# trezor_nuri.net
KiCad netlist of a schematic drawn in EAGLE
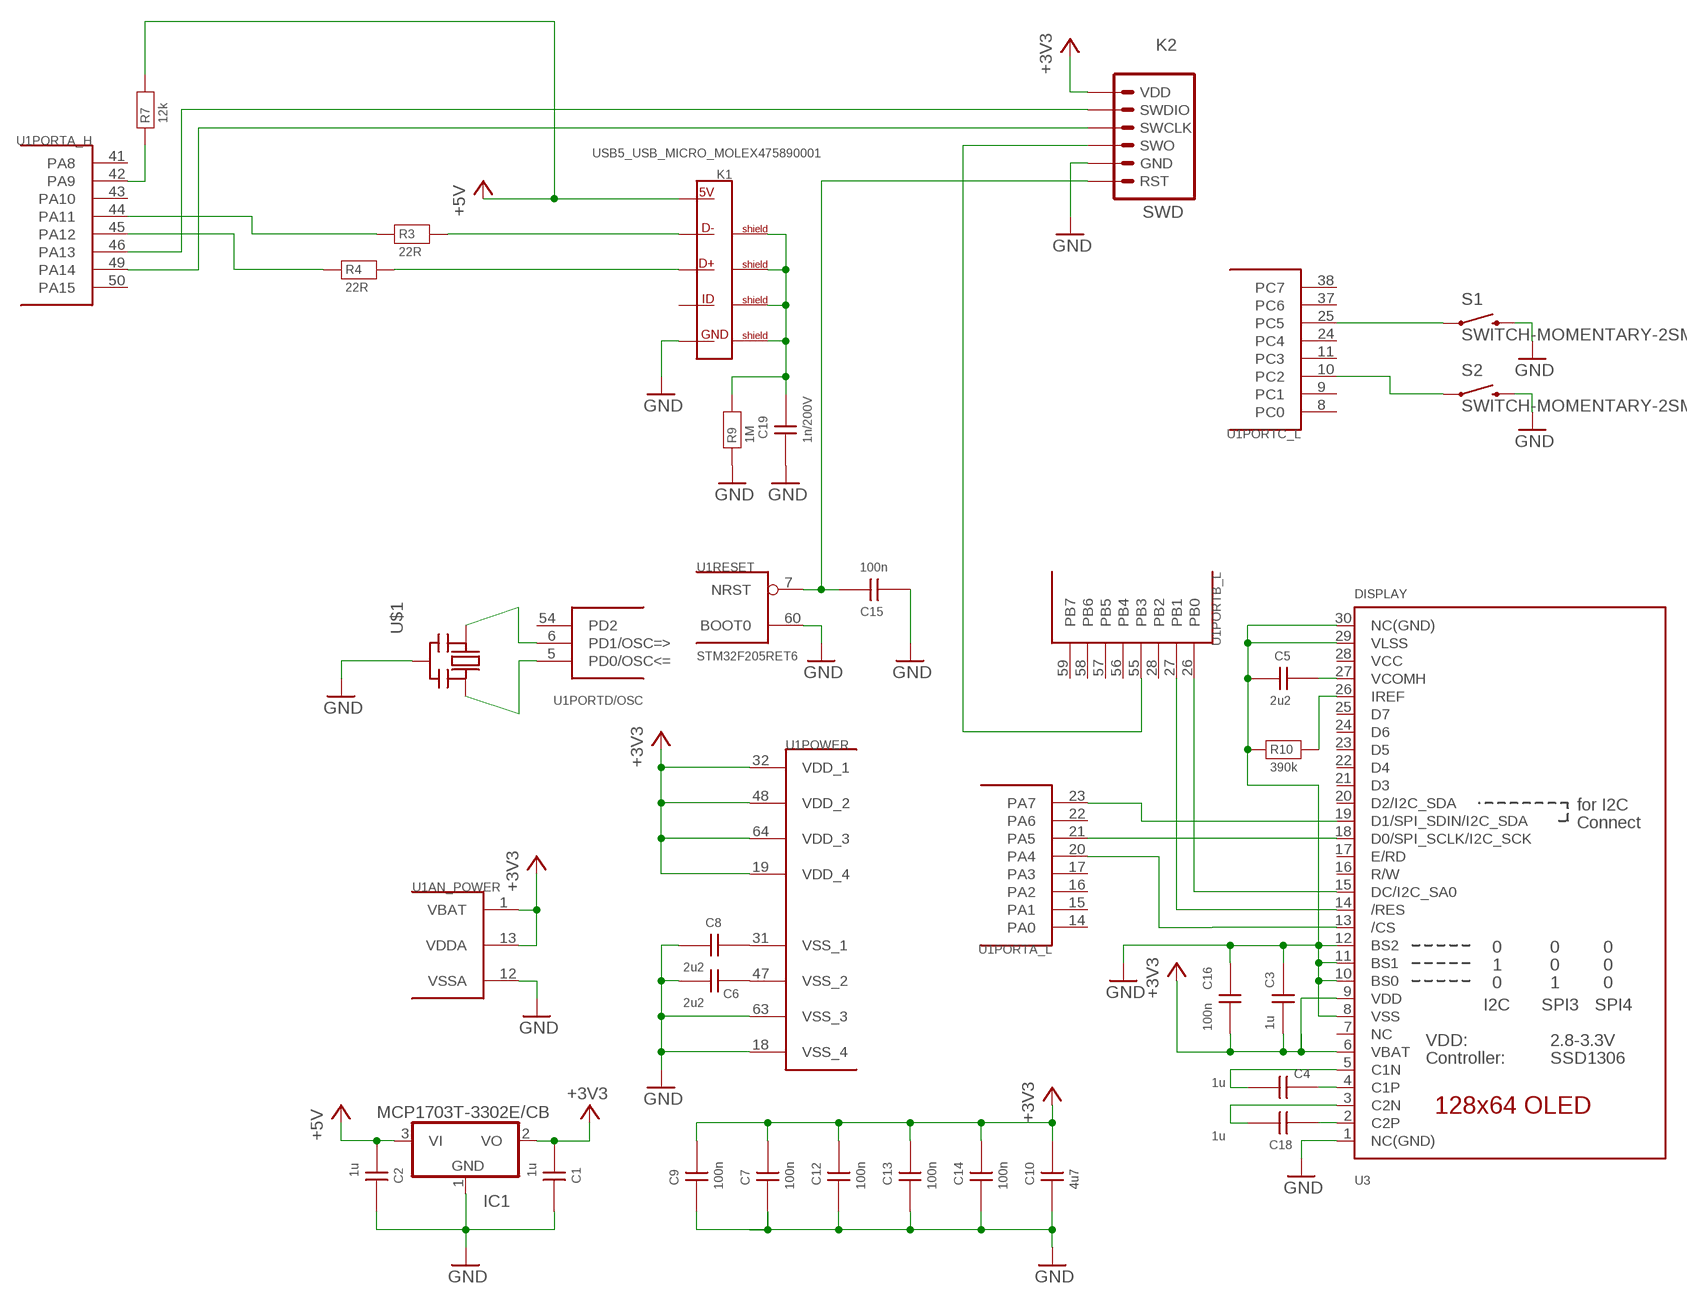
[diagram p0: schematic, sheet 1]

(export (version "E")
  (design (tool "Eeschema 10.0.6"))
  (components
    (comp (ref "C1")
      (value "1u")
      (footprint "eagle-import:0805")
      (libsource (lib "eagle-import") (part "C_0805"))
    )
    (comp (ref "C2")
      (value "1u")
      (footprint "eagle-import:0805")
      (libsource (lib "eagle-import") (part "C_0805"))
    )
    (comp (ref "C3")
      (value "1u")
      (footprint "eagle-import:0805")
      (libsource (lib "eagle-import") (part "C_0805"))
    )
    (comp (ref "C4")
      (value "1u")
      (footprint "eagle-import:0805")
      (libsource (lib "eagle-import") (part "C_0805"))
    )
    (comp (ref "C5")
      (value "2u2")
      (footprint "eagle-import:0805")
      (libsource (lib "eagle-import") (part "C_0805"))
    )
    (comp (ref "C6")
      (value "2u2")
      (footprint "eagle-import:0805")
      (libsource (lib "eagle-import") (part "C_0805"))
    )
    (comp (ref "C7")
      (value "100n")
      (footprint "eagle-import:0805")
      (libsource (lib "eagle-import") (part "C_0805"))
    )
    (comp (ref "C8")
      (value "2u2")
      (footprint "eagle-import:0805")
      (libsource (lib "eagle-import") (part "C_0805"))
    )
    (comp (ref "C9")
      (value "100n")
      (footprint "eagle-import:0805")
      (libsource (lib "eagle-import") (part "C_0805"))
    )
    (comp (ref "C10")
      (value "4u7")
      (footprint "eagle-import:0805")
      (libsource (lib "eagle-import") (part "C_0805"))
    )
    (comp (ref "C12")
      (value "100n")
      (footprint "eagle-import:0805")
      (libsource (lib "eagle-import") (part "C_0805"))
    )
    (comp (ref "C13")
      (value "100n")
      (footprint "eagle-import:0805")
      (libsource (lib "eagle-import") (part "C_0805"))
    )
    (comp (ref "C14")
      (value "100n")
      (footprint "eagle-import:0805")
      (libsource (lib "eagle-import") (part "C_0805"))
    )
    (comp (ref "C15")
      (value "100n")
      (footprint "eagle-import:0805")
      (libsource (lib "eagle-import") (part "C_0805"))
    )
    (comp (ref "C16")
      (value "100n")
      (footprint "eagle-import:0805")
      (libsource (lib "eagle-import") (part "C_0805"))
    )
    (comp (ref "C18")
      (value "1u")
      (footprint "eagle-import:0805")
      (libsource (lib "eagle-import") (part "C_0805"))
    )
    (comp (ref "C19")
      (value "1n/200V")
      (footprint "eagle-import:0805")
      (libsource (lib "eagle-import") (part "C_0805"))
    )
    (comp (ref "IC1")
      (value "MCP1703T-3302E/CB")
      (footprint "eagle-import:SOT23")
      (libsource (lib "eagle-import") (part "MCP1703CB"))
    )
    (comp (ref "K1")
      (value "USB5_USB_MICRO_MOLEX475890001")
      (footprint "eagle-import:USB_MICRO-MOLEX475890001")
      (libsource (lib "eagle-import") (part "USB5_USB_MICRO_MOLEX475890001"))
    )
    (comp (ref "K2")
      (value "SWD")
      (footprint "eagle-import:SWD")
      (libsource (lib "eagle-import") (part "SWD"))
    )
    (comp (ref "R3")
      (value "22R")
      (footprint "eagle-import:0805")
      (libsource (lib "eagle-import") (part "R_0805"))
    )
    (comp (ref "R4")
      (value "22R")
      (footprint "eagle-import:0805")
      (libsource (lib "eagle-import") (part "R_0805"))
    )
    (comp (ref "R7")
      (value "12k")
      (footprint "eagle-import:0805")
      (libsource (lib "eagle-import") (part "R_0805"))
    )
    (comp (ref "R9")
      (value "1M")
      (footprint "eagle-import:0805")
      (libsource (lib "eagle-import") (part "R_0805"))
    )
    (comp (ref "R10")
      (value "390k")
      (footprint "eagle-import:0805")
      (libsource (lib "eagle-import") (part "R_0805"))
    )
    (comp (ref "S1")
      (value "SWITCH-MOMENTARY-2SMD")
      (footprint "eagle-import:TACTILE_SWITCH_SMD")
      (libsource (lib "eagle-import") (part "SWITCH-MOMENTARY-2SMD"))
    )
    (comp (ref "S2")
      (value "SWITCH-MOMENTARY-2SMD")
      (footprint "eagle-import:TACTILE_SWITCH_SMD")
      (libsource (lib "eagle-import") (part "SWITCH-MOMENTARY-2SMD"))
    )
    (comp (ref "U$1")
      (value "CERMOSCILL-CSTCRG")
      (footprint "eagle-import:CSTCR-G")
      (libsource (lib "eagle-import") (part "CERMOSCILL-CSTCRG"))
    )
    (comp (ref "U1")
      (value "STM32F205RET6")
      (footprint "eagle-import:TQFP64")
      (libsource (lib "eagle-import") (part "STM32F10XRXT6"))
    )
    (comp (ref "U3")
      (value "DISPLAY")
      (footprint "eagle-import:UG-2864HSWEG01_0.96IN_WRAPAROUND")
      (libsource (lib "eagle-import") (part "DISP_OLED_UG-2864HSWEG010.96{dblquote}"))
    )
  )
  (nets
    (net (code "1") (name "+3V3") (class "Default")
      (node (ref "C1") (pin "1") (pinfunction "1_1") (pintype "passive"))
      (node (ref "C10") (pin "2") (pinfunction "2_2") (pintype "passive"))
      (node (ref "C12") (pin "2") (pinfunction "2_2") (pintype "passive"))
      (node (ref "C13") (pin "2") (pinfunction "2_2") (pintype "passive"))
      (node (ref "C14") (pin "2") (pinfunction "2_2") (pintype "passive"))
      (node (ref "C16") (pin "1") (pinfunction "1_1") (pintype "passive"))
      (node (ref "C3") (pin "1") (pinfunction "1_1") (pintype "passive"))
      (node (ref "C7") (pin "2") (pinfunction "2_2") (pintype "passive"))
      (node (ref "C9") (pin "2") (pinfunction "2_2") (pintype "passive"))
      (node (ref "IC1") (pin "2") (pinfunction "VO_2") (pintype "passive"))
      (node (ref "K2") (pin "6") (pinfunction "VDD_6") (pintype "passive"))
      (node (ref "U1") (pin "1") (pinfunction "VBAT_1") (pintype "power_in"))
      (node (ref "U1") (pin "13") (pinfunction "VDDA_13") (pintype "power_in"))
      (node (ref "U1") (pin "19") (pinfunction "VDD_4_19") (pintype "power_in"))
      (node (ref "U1") (pin "32") (pinfunction "VDD_1_32") (pintype "power_in"))
      (node (ref "U1") (pin "48") (pinfunction "VDD_2_48") (pintype "power_in"))
      (node (ref "U1") (pin "64") (pinfunction "VDD_3_64") (pintype "power_in"))
      (node (ref "U3") (pin "6") (pinfunction "VBAT_6") (pintype "input"))
      (node (ref "U3") (pin "9") (pinfunction "VDD_9") (pintype "power_in"))
    )
    (net (code "2") (name "+5V") (class "Default")
      (node (ref "C2") (pin "1") (pinfunction "1_1") (pintype "passive"))
      (node (ref "IC1") (pin "3") (pinfunction "VI_3") (pintype "input"))
      (node (ref "K1") (pin "1") (pinfunction "1_5V_1") (pintype "bidirectional"))
      (node (ref "R7") (pin "2") (pinfunction "2_2") (pintype "passive"))
    )
    (net (code "3") (name "/VCC") (class "Default")
      (node (ref "U3") (pin "28") (pinfunction "VCC_28") (pintype "power_in"))
    )
    (net (code "4") (name "GND") (class "Default")
      (node (ref "C1") (pin "2") (pinfunction "2_2") (pintype "passive"))
      (node (ref "C10") (pin "1") (pinfunction "1_1") (pintype "passive"))
      (node (ref "C12") (pin "1") (pinfunction "1_1") (pintype "passive"))
      (node (ref "C13") (pin "1") (pinfunction "1_1") (pintype "passive"))
      (node (ref "C14") (pin "1") (pinfunction "1_1") (pintype "passive"))
      (node (ref "C15") (pin "1") (pinfunction "1_1") (pintype "passive"))
      (node (ref "C16") (pin "2") (pinfunction "2_2") (pintype "passive"))
      (node (ref "C19") (pin "1") (pinfunction "1_1") (pintype "passive"))
      (node (ref "C2") (pin "2") (pinfunction "2_2") (pintype "passive"))
      (node (ref "C3") (pin "2") (pinfunction "2_2") (pintype "passive"))
      (node (ref "C5") (pin "1") (pinfunction "1_1") (pintype "passive"))
      (node (ref "C6") (pin "1") (pinfunction "1_1") (pintype "passive"))
      (node (ref "C7") (pin "1") (pinfunction "1_1") (pintype "passive"))
      (node (ref "C8") (pin "1") (pinfunction "1_1") (pintype "passive"))
      (node (ref "C9") (pin "1") (pinfunction "1_1") (pintype "passive"))
      (node (ref "IC1") (pin "1") (pinfunction "GND_1") (pintype "passive"))
      (node (ref "K1") (pin "5") (pinfunction "5_GND_5") (pintype "bidirectional"))
      (node (ref "K2") (pin "2") (pinfunction "GND_2") (pintype "passive"))
      (node (ref "R10") (pin "1") (pinfunction "1_1") (pintype "passive"))
      (node (ref "R9") (pin "1") (pinfunction "1_1") (pintype "passive"))
      (node (ref "S1") (pin "3") (pinfunction "2_3") (pintype "passive"))
      (node (ref "S1") (pin "4") (pinfunction "2_4") (pintype "passive"))
      (node (ref "S2") (pin "3") (pinfunction "2_3") (pintype "passive"))
      (node (ref "S2") (pin "4") (pinfunction "2_4") (pintype "passive"))
      (node (ref "U$1") (pin "2") (pinfunction "GND_2") (pintype "bidirectional"))
      (node (ref "U1") (pin "12") (pinfunction "VSSA_12") (pintype "power_in"))
      (node (ref "U1") (pin "18") (pinfunction "VSS_4_18") (pintype "power_in"))
      (node (ref "U1") (pin "60") (pinfunction "BOOT0_60") (pintype "input"))
      (node (ref "U1") (pin "63") (pinfunction "VSS_3_63") (pintype "power_in"))
      (node (ref "U3") (pin "1") (pinfunction "NC(GND)_1") (pintype "input"))
      (node (ref "U3") (pin "10") (pinfunction "BS0_10") (pintype "input"))
      (node (ref "U3") (pin "11") (pinfunction "BS1_11") (pintype "input"))
      (node (ref "U3") (pin "12") (pinfunction "BS2_12") (pintype "input"))
      (node (ref "U3") (pin "29") (pinfunction "VLSS_29") (pintype "power_in"))
      (node (ref "U3") (pin "30") (pinfunction "NC(GND)_30") (pintype "input"))
      (node (ref "U3") (pin "8") (pinfunction "VSS_8") (pintype "power_in"))
    )
    (net (code "5") (name "Net-(C19-Pad2)") (class "Default")
      (node (ref "C19") (pin "2") (pinfunction "2_2") (pintype "passive"))
      (node (ref "K1") (pin "S1_BOT") (pinfunction "SHIELD_1_S1_BOT") (pintype "passive"))
      (node (ref "K1") (pin "S1_TOP") (pinfunction "SHIELD_1_S1_TOP") (pintype "passive"))
      (node (ref "K1") (pin "S2_BOT") (pinfunction "SHIELD_2_S2_BOT") (pintype "passive"))
      (node (ref "K1") (pin "S2_TOP") (pinfunction "SHIELD_2_S2_TOP") (pintype "passive"))
      (node (ref "K1") (pin "S3_BOT") (pinfunction "SHIELD_3_S3_BOT") (pintype "passive"))
      (node (ref "K1") (pin "S3_TOP") (pinfunction "SHIELD_3_S3_TOP") (pintype "passive"))
      (node (ref "K1") (pin "S4_BOT") (pinfunction "SHIELD_4_S4_BOT") (pintype "passive"))
      (node (ref "K1") (pin "S4_TOP") (pinfunction "SHIELD_4_S4_TOP") (pintype "passive"))
      (node (ref "K1") (pin "SA") (pinfunction "SHIELD_1_SA") (pintype "passive"))
      (node (ref "K1") (pin "SB") (pinfunction "SHIELD_2_SB") (pintype "passive"))
      (node (ref "R9") (pin "2") (pinfunction "2_2") (pintype "passive"))
    )
    (net (code "6") (name "Net-(K1-2_D-)") (class "Default")
      (node (ref "K1") (pin "2") (pinfunction "2_D-_2") (pintype "bidirectional"))
      (node (ref "R3") (pin "2") (pinfunction "2_2") (pintype "passive"))
    )
    (net (code "7") (name "Net-(K1-3_D+)") (class "Default")
      (node (ref "K1") (pin "3") (pinfunction "3_D+_3") (pintype "bidirectional"))
      (node (ref "R4") (pin "2") (pinfunction "2_2") (pintype "passive"))
    )
    (net (code "8") (name "Net-(K2-RST)") (class "Default")
      (node (ref "C15") (pin "2") (pinfunction "2_2") (pintype "passive"))
      (node (ref "K2") (pin "1") (pinfunction "RST_1") (pintype "passive"))
      (node (ref "U1") (pin "7") (pinfunction "NRST_7") (pintype "input"))
    )
    (net (code "9") (name "Net-(K2-SWCLK)") (class "Default")
      (node (ref "K2") (pin "4") (pinfunction "SWCLK_4") (pintype "passive"))
      (node (ref "U1") (pin "49") (pinfunction "PA14_49") (pintype "bidirectional"))
    )
    (net (code "10") (name "Net-(K2-SWDIO)") (class "Default")
      (node (ref "K2") (pin "5") (pinfunction "SWDIO_5") (pintype "passive"))
      (node (ref "U1") (pin "46") (pinfunction "PA13_46") (pintype "bidirectional"))
    )
    (net (code "11") (name "Net-(K2-SWO)") (class "Default")
      (node (ref "K2") (pin "3") (pinfunction "SWO_3") (pintype "passive"))
      (node (ref "U1") (pin "55") (pinfunction "PB3_55") (pintype "bidirectional"))
    )
    (net (code "12") (name "Net-(U$1-IN)") (class "Default")
      (node (ref "U$1") (pin "1") (pinfunction "IN_1") (pintype "bidirectional"))
      (node (ref "U1") (pin "6") (pinfunction "PD1/OSC=>_6") (pintype "bidirectional"))
    )
    (net (code "13") (name "Net-(U$1-OUT)") (class "Default")
      (node (ref "U$1") (pin "3") (pinfunction "OUT_3") (pintype "bidirectional"))
      (node (ref "U1") (pin "5") (pinfunction "PD0/OSC<=_5") (pintype "bidirectional"))
    )
    (net (code "14") (name "Net-(U1B-PA9)") (class "Default")
      (node (ref "R7") (pin "1") (pinfunction "1_1") (pintype "passive"))
      (node (ref "U1") (pin "42") (pinfunction "PA9_42") (pintype "bidirectional"))
    )
    (net (code "15") (name "Net-(U1B-PA11)") (class "Default")
      (node (ref "R3") (pin "1") (pinfunction "1_1") (pintype "passive"))
      (node (ref "U1") (pin "44") (pinfunction "PA11_44") (pintype "bidirectional"))
    )
    (net (code "16") (name "Net-(U1B-PA12)") (class "Default")
      (node (ref "R4") (pin "1") (pinfunction "1_1") (pintype "passive"))
      (node (ref "U1") (pin "45") (pinfunction "PA12_45") (pintype "bidirectional"))
    )
    (net (code "17") (name "Net-(U1C-PA4)") (class "Default")
      (node (ref "U1") (pin "20") (pinfunction "PA4_20") (pintype "bidirectional"))
      (node (ref "U3") (pin "13") (pinfunction "/CS_13") (pintype "input"))
    )
    (net (code "18") (name "Net-(U1C-PA5)") (class "Default")
      (node (ref "U1") (pin "21") (pinfunction "PA5_21") (pintype "bidirectional"))
      (node (ref "U3") (pin "18") (pinfunction "D0/SPI_SCLK/I2C_SCK_18") (pintype "bidirectional"))
    )
    (net (code "19") (name "Net-(U1C-PA7)") (class "Default")
      (node (ref "U1") (pin "23") (pinfunction "PA7_23") (pintype "bidirectional"))
      (node (ref "U3") (pin "19") (pinfunction "D1/SPI_SDIN/I2C_SDA_19") (pintype "bidirectional"))
    )
    (net (code "20") (name "Net-(U1E-PB0)") (class "Default")
      (node (ref "U1") (pin "26") (pinfunction "PB0_26") (pintype "bidirectional"))
      (node (ref "U3") (pin "15") (pinfunction "DC/I2C_SA0_15") (pintype "input"))
    )
    (net (code "21") (name "Net-(U1E-PB1)") (class "Default")
      (node (ref "U1") (pin "27") (pinfunction "PB1_27") (pintype "bidirectional"))
      (node (ref "U3") (pin "14") (pinfunction "/RES_14") (pintype "input"))
    )
    (net (code "22") (name "Net-(U1G-PC2)") (class "Default")
      (node (ref "S2") (pin "1") (pinfunction "1_1") (pintype "passive"))
      (node (ref "S2") (pin "2") (pinfunction "1_2") (pintype "passive"))
      (node (ref "U1") (pin "10") (pinfunction "PC2_10") (pintype "bidirectional"))
    )
    (net (code "23") (name "Net-(U1G-PC5)") (class "Default")
      (node (ref "S1") (pin "1") (pinfunction "1_1") (pintype "passive"))
      (node (ref "S1") (pin "2") (pinfunction "1_2") (pintype "passive"))
      (node (ref "U1") (pin "25") (pinfunction "PC5_25") (pintype "bidirectional"))
    )
    (net (code "24") (name "Net-(U1I-VSS_1)") (class "Default")
      (node (ref "C8") (pin "2") (pinfunction "2_2") (pintype "passive"))
      (node (ref "U1") (pin "31") (pinfunction "VSS_1_31") (pintype "power_in"))
    )
    (net (code "25") (name "Net-(U1I-VSS_2)") (class "Default")
      (node (ref "C6") (pin "2") (pinfunction "2_2") (pintype "passive"))
      (node (ref "U1") (pin "47") (pinfunction "VSS_2_47") (pintype "power_in"))
    )
    (net (code "26") (name "Net-(U3-C1N)") (class "Default")
      (node (ref "C4") (pin "2") (pinfunction "2_2") (pintype "passive"))
      (node (ref "U3") (pin "5") (pinfunction "C1N_5") (pintype "input"))
    )
    (net (code "27") (name "Net-(U3-C1P)") (class "Default")
      (node (ref "C4") (pin "1") (pinfunction "1_1") (pintype "passive"))
      (node (ref "U3") (pin "4") (pinfunction "C1P_4") (pintype "input"))
    )
    (net (code "28") (name "Net-(U3-C2N)") (class "Default")
      (node (ref "C18") (pin "2") (pinfunction "2_2") (pintype "passive"))
      (node (ref "U3") (pin "3") (pinfunction "C2N_3") (pintype "input"))
    )
    (net (code "29") (name "Net-(U3-C2P)") (class "Default")
      (node (ref "C18") (pin "1") (pinfunction "1_1") (pintype "passive"))
      (node (ref "U3") (pin "2") (pinfunction "C2P_2") (pintype "input"))
    )
    (net (code "30") (name "Net-(U3-IREF)") (class "Default")
      (node (ref "R10") (pin "2") (pinfunction "2_2") (pintype "passive"))
      (node (ref "U3") (pin "26") (pinfunction "IREF_26") (pintype "input"))
    )
    (net (code "31") (name "Net-(U3-VCOMH)") (class "Default")
      (node (ref "C5") (pin "2") (pinfunction "2_2") (pintype "passive"))
      (node (ref "U3") (pin "27") (pinfunction "VCOMH_27") (pintype "output"))
    )
    (net (code "32") (name "unconnected-(K1-4_ID-Pad4)") (class "Default")
      (node (ref "K1") (pin "4") (pinfunction "4_ID_4") (pintype "bidirectional"))
    )
    (net (code "33") (name "unconnected-(U1B-PA8-Pad41)") (class "Default")
      (node (ref "U1") (pin "41") (pinfunction "PA8_41") (pintype "bidirectional"))
    )
    (net (code "34") (name "unconnected-(U1B-PA10-Pad43)") (class "Default")
      (node (ref "U1") (pin "43") (pinfunction "PA10_43") (pintype "bidirectional"))
    )
    (net (code "35") (name "unconnected-(U1B-PA15-Pad50)") (class "Default")
      (node (ref "U1") (pin "50") (pinfunction "PA15_50") (pintype "bidirectional"))
    )
    (net (code "36") (name "unconnected-(U1C-PA0-Pad14)") (class "Default")
      (node (ref "U1") (pin "14") (pinfunction "PA0_14") (pintype "bidirectional"))
    )
    (net (code "37") (name "unconnected-(U1C-PA1-Pad15)") (class "Default")
      (node (ref "U1") (pin "15") (pinfunction "PA1_15") (pintype "bidirectional"))
    )
    (net (code "38") (name "unconnected-(U1C-PA2-Pad16)") (class "Default")
      (node (ref "U1") (pin "16") (pinfunction "PA2_16") (pintype "bidirectional"))
    )
    (net (code "39") (name "unconnected-(U1C-PA3-Pad17)") (class "Default")
      (node (ref "U1") (pin "17") (pinfunction "PA3_17") (pintype "bidirectional"))
    )
    (net (code "40") (name "unconnected-(U1C-PA6-Pad22)") (class "Default")
      (node (ref "U1") (pin "22") (pinfunction "PA6_22") (pintype "bidirectional"))
    )
    (net (code "41") (name "unconnected-(U1E-PB2-Pad28)") (class "Default")
      (node (ref "U1") (pin "28") (pinfunction "PB2_28") (pintype "bidirectional"))
    )
    (net (code "42") (name "unconnected-(U1E-PB4-Pad56)") (class "Default")
      (node (ref "U1") (pin "56") (pinfunction "PB4_56") (pintype "bidirectional"))
    )
    (net (code "43") (name "unconnected-(U1E-PB5-Pad57)") (class "Default")
      (node (ref "U1") (pin "57") (pinfunction "PB5_57") (pintype "bidirectional"))
    )
    (net (code "44") (name "unconnected-(U1E-PB6-Pad58)") (class "Default")
      (node (ref "U1") (pin "58") (pinfunction "PB6_58") (pintype "bidirectional"))
    )
    (net (code "45") (name "unconnected-(U1E-PB7-Pad59)") (class "Default")
      (node (ref "U1") (pin "59") (pinfunction "PB7_59") (pintype "bidirectional"))
    )
    (net (code "46") (name "unconnected-(U1G-PC0-Pad8)") (class "Default")
      (node (ref "U1") (pin "8") (pinfunction "PC0_8") (pintype "bidirectional"))
    )
    (net (code "47") (name "unconnected-(U1G-PC1-Pad9)") (class "Default")
      (node (ref "U1") (pin "9") (pinfunction "PC1_9") (pintype "bidirectional"))
    )
    (net (code "48") (name "unconnected-(U1G-PC3-Pad11)") (class "Default")
      (node (ref "U1") (pin "11") (pinfunction "PC3_11") (pintype "bidirectional"))
    )
    (net (code "49") (name "unconnected-(U1G-PC4-Pad24)") (class "Default")
      (node (ref "U1") (pin "24") (pinfunction "PC4_24") (pintype "bidirectional"))
    )
    (net (code "50") (name "unconnected-(U1G-PC6-Pad37)") (class "Default")
      (node (ref "U1") (pin "37") (pinfunction "PC6_37") (pintype "bidirectional"))
    )
    (net (code "51") (name "unconnected-(U1G-PC7-Pad38)") (class "Default")
      (node (ref "U1") (pin "38") (pinfunction "PC7_38") (pintype "bidirectional"))
    )
    (net (code "52") (name "unconnected-(U1H-PD2-Pad54)") (class "Default")
      (node (ref "U1") (pin "54") (pinfunction "PD2_54") (pintype "bidirectional"))
    )
    (net (code "53") (name "unconnected-(U3-D2{slash}I2C_SDA-Pad20)") (class "Default")
      (node (ref "U3") (pin "20") (pinfunction "D2/I2C_SDA_20") (pintype "bidirectional"))
    )
    (net (code "54") (name "unconnected-(U3-D3-Pad21)") (class "Default")
      (node (ref "U3") (pin "21") (pinfunction "D3_21") (pintype "bidirectional"))
    )
    (net (code "55") (name "unconnected-(U3-D4-Pad22)") (class "Default")
      (node (ref "U3") (pin "22") (pinfunction "D4_22") (pintype "bidirectional"))
    )
    (net (code "56") (name "unconnected-(U3-D5-Pad23)") (class "Default")
      (node (ref "U3") (pin "23") (pinfunction "D5_23") (pintype "bidirectional"))
    )
    (net (code "57") (name "unconnected-(U3-D6-Pad24)") (class "Default")
      (node (ref "U3") (pin "24") (pinfunction "D6_24") (pintype "bidirectional"))
    )
    (net (code "58") (name "unconnected-(U3-D7-Pad25)") (class "Default")
      (node (ref "U3") (pin "25") (pinfunction "D7_25") (pintype "bidirectional"))
    )
    (net (code "59") (name "unconnected-(U3-E{slash}RD-Pad17)") (class "Default")
      (node (ref "U3") (pin "17") (pinfunction "E/RD_17") (pintype "input"))
    )
    (net (code "60") (name "unconnected-(U3-NC-Pad7)") (class "Default")
      (node (ref "U3") (pin "7") (pinfunction "NC_7") (pintype "no_connect"))
    )
    (net (code "61") (name "unconnected-(U3-R{slash}W-Pad16)") (class "Default")
      (node (ref "U3") (pin "16") (pinfunction "R/W_16") (pintype "input"))
    )
  )
)
